# DIO_3.net
KiCad netlist of a schematic drawn in Altium Designer
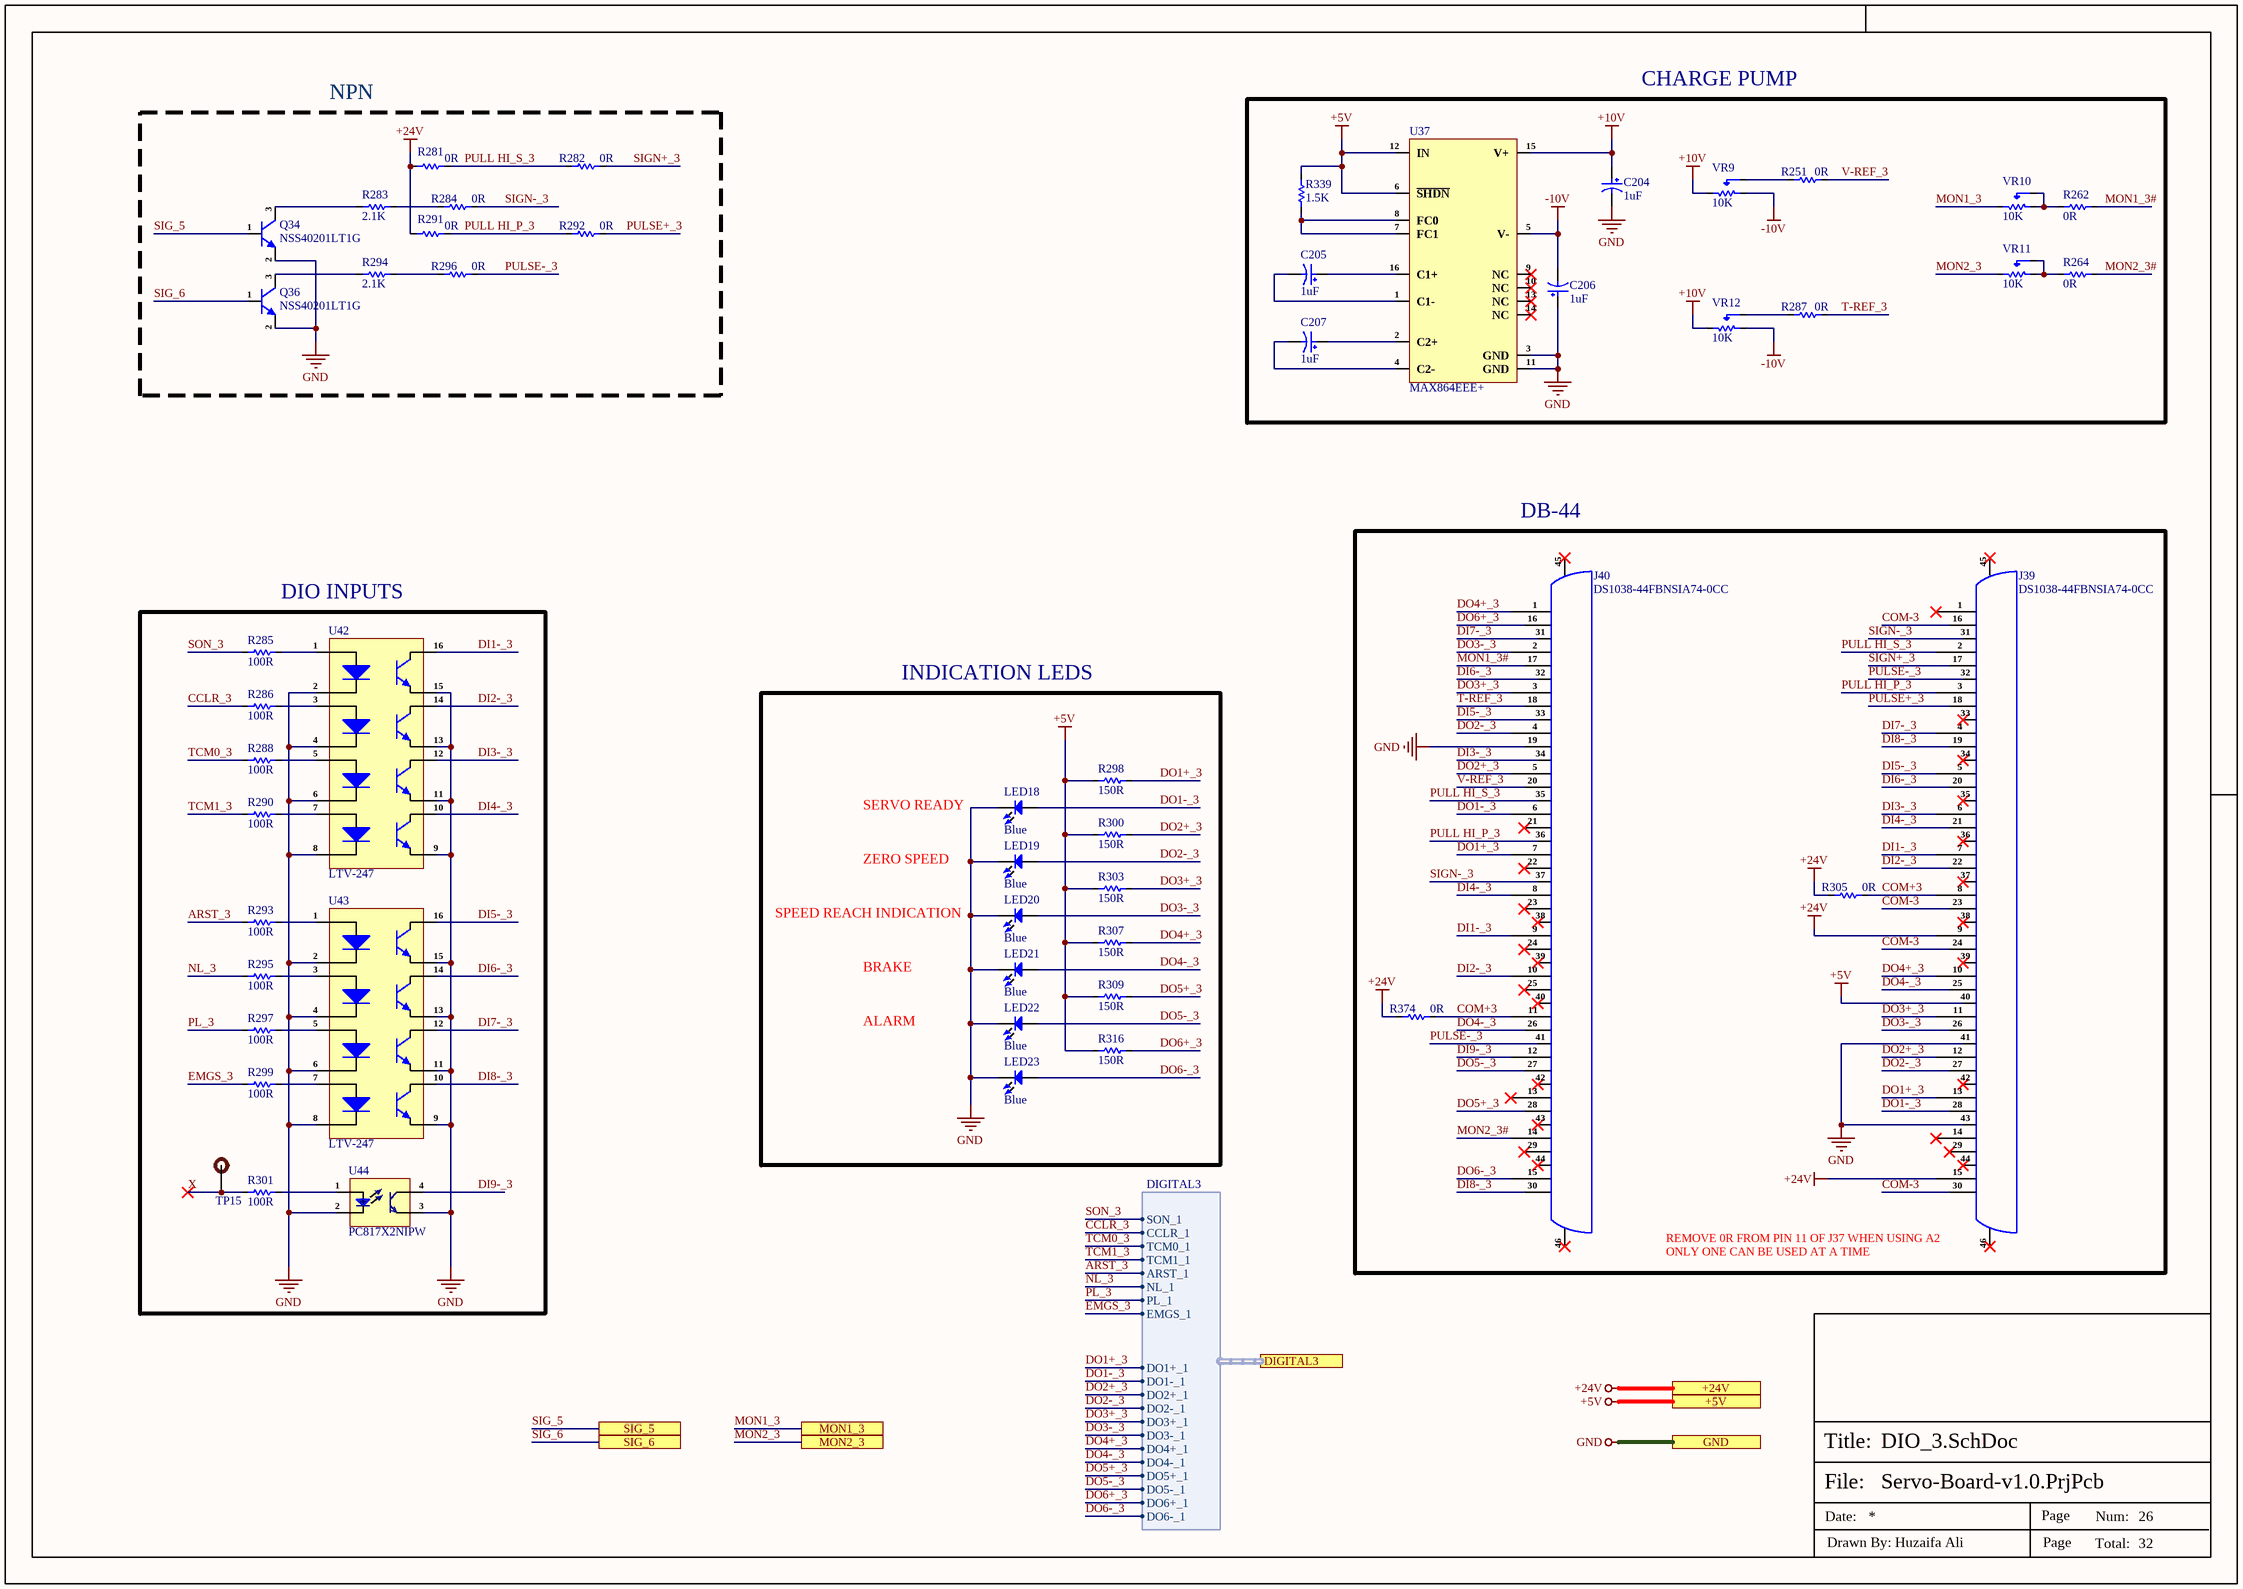
[diagram p0: DIO_3.SchDoc]

(export (version "E")
  (design (tool "Eeschema 10.0.6"))
  (components
    (comp (ref "C204")
      (value "1uF")
      (footprint "RVT1H1R0M0405")
      (description "1uF 50V 8mA@120Hz ±20% SMD,D4xL5.4mm Aluminum Electrolytic Capacitors - SMD ROHS")
      (fields (field (name "LCSC PART NUMBER") "C72491") (field (name "MANUFACTURER") "Roqang"))
      (libsource (lib "") (part "RVT1H1R0M0405_1"))
    )
    (comp (ref "C205")
      (value "1uF")
      (footprint "RVT1H1R0M0405")
      (description "1uF 50V 8mA@120Hz ±20% SMD,D4xL5.4mm Aluminum Electrolytic Capacitors - SMD ROHS")
      (fields (field (name "LCSC PART NUMBER") "C72491") (field (name "MANUFACTURER") "Roqang"))
      (libsource (lib "") (part "RVT1H1R0M0405_2"))
    )
    (comp (ref "C206")
      (value "1uF")
      (footprint "RVT1H1R0M0405")
      (description "1uF 50V 8mA@120Hz ±20% SMD,D4xL5.4mm Aluminum Electrolytic Capacitors - SMD ROHS")
      (fields (field (name "LCSC PART NUMBER") "C72491") (field (name "MANUFACTURER") "Roqang"))
      (libsource (lib "eSpark Libraries") (part "RVT1H1R0M0405"))
    )
    (comp (ref "C207")
      (value "1uF")
      (footprint "RVT1H1R0M0405")
      (description "1uF 50V 8mA@120Hz ±20% SMD,D4xL5.4mm Aluminum Electrolytic Capacitors - SMD ROHS")
      (fields (field (name "LCSC PART NUMBER") "C72491") (field (name "MANUFACTURER") "Roqang"))
      (libsource (lib "") (part "RVT1H1R0M0405_2"))
    )
    (comp (ref "J39")
      (value "DS1038-44FBNSIA74-0CC")
      (footprint "DS1038-44FBNSIA74-0CC")
      (description "44P Female D-Sub Right-Angle 3 1.5A -40℃~+105℃ Push-Pull D-Sub / VGA connector ROHS")
      (fields (field (name "MANUFACTURER") "CONNFLY Elec") (field (name "LCSC PART NUMBER") "C77844"))
      (libsource (lib "eSpark Libraries") (part "DS1038-44FBNSIA74-0CC"))
    )
    (comp (ref "J40")
      (value "DS1038-44FBNSIA74-0CC")
      (footprint "DS1038-44FBNSIA74-0CC")
      (description "44P Female D-Sub Right-Angle 3 1.5A -40℃~+105℃ Push-Pull D-Sub / VGA connector ROHS")
      (fields (field (name "MANUFACTURER") "CONNFLY Elec") (field (name "LCSC PART NUMBER") "C77844"))
      (libsource (lib "eSpark Libraries") (part "DS1038-44FBNSIA74-0CC"))
    )
    (comp (ref "LED18")
      (value "Blue")
      (footprint "LED-0603")
      (description "blue 0603 Light Emitting Diodes (LED) ROHS")
      (fields
        (field (name "MANUFACTURER") "Foshan NationStar Optoelectronics")
        (field (name "MANUFACTURER PART NUMBER") "NCD0603B3")
      )
      (libsource (lib "eSpark Libraries") (part "NCD0603B3"))
    )
    (comp (ref "LED19")
      (value "Blue")
      (footprint "LED-0603")
      (description "blue 0603 Light Emitting Diodes (LED) ROHS")
      (fields
        (field (name "MANUFACTURER") "Foshan NationStar Optoelectronics")
        (field (name "MANUFACTURER PART NUMBER") "NCD0603B3")
      )
      (libsource (lib "eSpark Libraries") (part "NCD0603B3"))
    )
    (comp (ref "LED20")
      (value "Blue")
      (footprint "LED-0603")
      (description "blue 0603 Light Emitting Diodes (LED) ROHS")
      (fields
        (field (name "MANUFACTURER") "Foshan NationStar Optoelectronics")
        (field (name "MANUFACTURER PART NUMBER") "NCD0603B3")
      )
      (libsource (lib "eSpark Libraries") (part "NCD0603B3"))
    )
    (comp (ref "LED21")
      (value "Blue")
      (footprint "LED-0603")
      (description "blue 0603 Light Emitting Diodes (LED) ROHS")
      (fields
        (field (name "MANUFACTURER") "Foshan NationStar Optoelectronics")
        (field (name "MANUFACTURER PART NUMBER") "NCD0603B3")
      )
      (libsource (lib "eSpark Libraries") (part "NCD0603B3"))
    )
    (comp (ref "LED22")
      (value "Blue")
      (footprint "LED-0603")
      (description "blue 0603 Light Emitting Diodes (LED) ROHS")
      (fields
        (field (name "MANUFACTURER") "Foshan NationStar Optoelectronics")
        (field (name "MANUFACTURER PART NUMBER") "NCD0603B3")
      )
      (libsource (lib "eSpark Libraries") (part "NCD0603B3"))
    )
    (comp (ref "LED23")
      (value "Blue")
      (footprint "LED-0603")
      (description "blue 0603 Light Emitting Diodes (LED) ROHS")
      (fields
        (field (name "MANUFACTURER") "Foshan NationStar Optoelectronics")
        (field (name "MANUFACTURER PART NUMBER") "NCD0603B3")
      )
      (libsource (lib "eSpark Libraries") (part "NCD0603B3"))
    )
    (comp (ref "Q34")
      (value "NSS40201LT1G")
      (footprint "SOT-23")
      (description "TRANS NPN 40V 2A SOT23-3")
      (fields (field (name "MANUFACTURER") "ON Semiconductor") (field (name "LCSC PART NUMBER") "C145175"))
      (libsource (lib "eSpark Libraries") (part "NSS40201LT1G"))
    )
    (comp (ref "Q36")
      (value "NSS40201LT1G")
      (footprint "SOT-23")
      (description "TRANS NPN 40V 2A SOT23-3")
      (fields (field (name "MANUFACTURER") "ON Semiconductor") (field (name "LCSC PART NUMBER") "C145175"))
      (libsource (lib "eSpark Libraries") (part "NSS40201LT1G"))
    )
    (comp (ref "R251")
      (value "0R")
      (footprint "Res-0402")
      (description "RES 0 OHM JUMPER 1/16W 0402")
      (fields
        (field (name "MANUFACTURER") "Yageo")
        (field (name "MANUFACTURER PART NUMBER") "RC0402FR-070RL")
      )
      (libsource (lib "eSpark Libraries") (part "RC0402FR-070RL"))
    )
    (comp (ref "R262")
      (value "0R")
      (footprint "Res-0402")
      (description "RES 0 OHM JUMPER 1/16W 0402")
      (fields
        (field (name "MANUFACTURER") "Yageo")
        (field (name "MANUFACTURER PART NUMBER") "RC0402FR-070RL")
      )
      (libsource (lib "eSpark Libraries") (part "RC0402FR-070RL"))
    )
    (comp (ref "R264")
      (value "0R")
      (footprint "Res-0402")
      (description "RES 0 OHM JUMPER 1/16W 0402")
      (fields
        (field (name "MANUFACTURER") "Yageo")
        (field (name "MANUFACTURER PART NUMBER") "RC0402FR-070RL")
      )
      (libsource (lib "eSpark Libraries") (part "RC0402FR-070RL"))
    )
    (comp (ref "R281")
      (value "0R")
      (footprint "Res-0603")
      (description "RES 0 OHM JUMPER 1/10W 0603")
      (fields
        (field (name "MANUFACTURER") "Yageo")
        (field (name "MANUFACTURER PART NUMBER") "RC0603JR-070RL")
      )
      (libsource (lib "eSpark Libraries") (part "RC0603JR-070RL"))
    )
    (comp (ref "R282")
      (value "0R")
      (footprint "Res-0603")
      (description "RES 0 OHM JUMPER 1/10W 0603")
      (fields
        (field (name "MANUFACTURER") "Yageo")
        (field (name "MANUFACTURER PART NUMBER") "RC0603JR-070RL")
      )
      (libsource (lib "eSpark Libraries") (part "RC0603JR-070RL"))
    )
    (comp (ref "R283")
      (value "2.1K")
      (footprint "Res-0603")
      (description "RES SMD 2.1K OHM 0.1% 1/10W 0603")
      (fields
        (field (name "MANUFACTURER") "Yageo")
        (field (name "MANUFACTURER PART NUMBER") "RT0603BRD072K1L")
      )
      (libsource (lib "eSpark Libraries") (part "RT0603BRD072K1L"))
    )
    (comp (ref "R284")
      (value "0R")
      (footprint "Res-0603")
      (description "RES 0 OHM JUMPER 1/10W 0603")
      (fields
        (field (name "MANUFACTURER") "Yageo")
        (field (name "MANUFACTURER PART NUMBER") "RC0603JR-070RL")
      )
      (libsource (lib "eSpark Libraries") (part "RC0603JR-070RL"))
    )
    (comp (ref "R285")
      (value "100R")
      (footprint "Res-0402")
      (description "RES 100 OHM 1% 1/16W 0402")
      (fields
        (field (name "MANUFACTURER") "Yageo")
        (field (name "MANUFACTURER PART NUMBER") "RC0402FR-07100RL")
      )
      (libsource (lib "eSpark Libraries") (part "RC0402FR-07100RL"))
    )
    (comp (ref "R286")
      (value "100R")
      (footprint "Res-0402")
      (description "RES 100 OHM 1% 1/16W 0402")
      (fields
        (field (name "MANUFACTURER") "Yageo")
        (field (name "MANUFACTURER PART NUMBER") "RC0402FR-07100RL")
      )
      (libsource (lib "eSpark Libraries") (part "RC0402FR-07100RL"))
    )
    (comp (ref "R287")
      (value "0R")
      (footprint "Res-0402")
      (description "RES 0 OHM JUMPER 1/16W 0402")
      (fields
        (field (name "MANUFACTURER") "Yageo")
        (field (name "MANUFACTURER PART NUMBER") "RC0402FR-070RL")
      )
      (libsource (lib "eSpark Libraries") (part "RC0402FR-070RL"))
    )
    (comp (ref "R288")
      (value "100R")
      (footprint "Res-0402")
      (description "RES 100 OHM 1% 1/16W 0402")
      (fields
        (field (name "MANUFACTURER") "Yageo")
        (field (name "MANUFACTURER PART NUMBER") "RC0402FR-07100RL")
      )
      (libsource (lib "eSpark Libraries") (part "RC0402FR-07100RL"))
    )
    (comp (ref "R290")
      (value "100R")
      (footprint "Res-0402")
      (description "RES 100 OHM 1% 1/16W 0402")
      (fields
        (field (name "MANUFACTURER") "Yageo")
        (field (name "MANUFACTURER PART NUMBER") "RC0402FR-07100RL")
      )
      (libsource (lib "eSpark Libraries") (part "RC0402FR-07100RL"))
    )
    (comp (ref "R291")
      (value "0R")
      (footprint "Res-0603")
      (description "RES 0 OHM JUMPER 1/10W 0603")
      (fields
        (field (name "MANUFACTURER") "Yageo")
        (field (name "MANUFACTURER PART NUMBER") "RC0603JR-070RL")
      )
      (libsource (lib "eSpark Libraries") (part "RC0603JR-070RL"))
    )
    (comp (ref "R292")
      (value "0R")
      (footprint "Res-0603")
      (description "RES 0 OHM JUMPER 1/10W 0603")
      (fields
        (field (name "MANUFACTURER") "Yageo")
        (field (name "MANUFACTURER PART NUMBER") "RC0603JR-070RL")
      )
      (libsource (lib "eSpark Libraries") (part "RC0603JR-070RL"))
    )
    (comp (ref "R293")
      (value "100R")
      (footprint "Res-0402")
      (description "RES 100 OHM 1% 1/16W 0402")
      (fields
        (field (name "MANUFACTURER") "Yageo")
        (field (name "MANUFACTURER PART NUMBER") "RC0402FR-07100RL")
      )
      (libsource (lib "eSpark Libraries") (part "RC0402FR-07100RL"))
    )
    (comp (ref "R294")
      (value "2.1K")
      (footprint "Res-0603")
      (description "RES SMD 2.1K OHM 0.1% 1/10W 0603")
      (fields
        (field (name "MANUFACTURER") "Yageo")
        (field (name "MANUFACTURER PART NUMBER") "RT0603BRD072K1L")
      )
      (libsource (lib "eSpark Libraries") (part "RT0603BRD072K1L"))
    )
    (comp (ref "R295")
      (value "100R")
      (footprint "Res-0402")
      (description "RES 100 OHM 1% 1/16W 0402")
      (fields
        (field (name "MANUFACTURER") "Yageo")
        (field (name "MANUFACTURER PART NUMBER") "RC0402FR-07100RL")
      )
      (libsource (lib "eSpark Libraries") (part "RC0402FR-07100RL"))
    )
    (comp (ref "R296")
      (value "0R")
      (footprint "Res-0603")
      (description "RES 0 OHM JUMPER 1/10W 0603")
      (fields
        (field (name "MANUFACTURER") "Yageo")
        (field (name "MANUFACTURER PART NUMBER") "RC0603JR-070RL")
      )
      (libsource (lib "eSpark Libraries") (part "RC0603JR-070RL"))
    )
    (comp (ref "R297")
      (value "100R")
      (footprint "Res-0402")
      (description "RES 100 OHM 1% 1/16W 0402")
      (fields
        (field (name "MANUFACTURER") "Yageo")
        (field (name "MANUFACTURER PART NUMBER") "RC0402FR-07100RL")
      )
      (libsource (lib "eSpark Libraries") (part "RC0402FR-07100RL"))
    )
    (comp (ref "R298")
      (value "150R")
      (footprint "Res-0603")
      (description "RES 150 OHM 0.5% 1/10W 0603")
      (fields
        (field (name "MANUFACTURER") "Yageo")
        (field (name "MANUFACTURER PART NUMBER") "RC0603DR-07150RL")
      )
      (libsource (lib "eSpark Libraries") (part "RC0603DR-07150RL"))
    )
    (comp (ref "R299")
      (value "100R")
      (footprint "Res-0402")
      (description "RES 100 OHM 1% 1/16W 0402")
      (fields
        (field (name "MANUFACTURER") "Yageo")
        (field (name "MANUFACTURER PART NUMBER") "RC0402FR-07100RL")
      )
      (libsource (lib "eSpark Libraries") (part "RC0402FR-07100RL"))
    )
    (comp (ref "R300")
      (value "150R")
      (footprint "Res-0603")
      (description "RES 150 OHM 0.5% 1/10W 0603")
      (fields
        (field (name "MANUFACTURER") "Yageo")
        (field (name "MANUFACTURER PART NUMBER") "RC0603DR-07150RL")
      )
      (libsource (lib "eSpark Libraries") (part "RC0603DR-07150RL"))
    )
    (comp (ref "R301")
      (value "100R")
      (footprint "Res-0402")
      (description "RES 100 OHM 1% 1/16W 0402")
      (fields
        (field (name "MANUFACTURER") "Yageo")
        (field (name "MANUFACTURER PART NUMBER") "RC0402FR-07100RL")
      )
      (libsource (lib "eSpark Libraries") (part "RC0402FR-07100RL"))
    )
    (comp (ref "R303")
      (value "150R")
      (footprint "Res-0603")
      (description "RES 150 OHM 0.5% 1/10W 0603")
      (fields
        (field (name "MANUFACTURER") "Yageo")
        (field (name "MANUFACTURER PART NUMBER") "RC0603DR-07150RL")
      )
      (libsource (lib "eSpark Libraries") (part "RC0603DR-07150RL"))
    )
    (comp (ref "R305")
      (value "0R")
      (footprint "Res-0402")
      (description "RES 0 OHM JUMPER 1/16W 0402")
      (fields
        (field (name "MANUFACTURER") "Yageo")
        (field (name "MANUFACTURER PART NUMBER") "RC0402FR-070RL")
      )
      (libsource (lib "eSpark Libraries") (part "RC0402FR-070RL"))
    )
    (comp (ref "R307")
      (value "150R")
      (footprint "Res-0603")
      (description "RES 150 OHM 0.5% 1/10W 0603")
      (fields
        (field (name "MANUFACTURER") "Yageo")
        (field (name "MANUFACTURER PART NUMBER") "RC0603DR-07150RL")
      )
      (libsource (lib "eSpark Libraries") (part "RC0603DR-07150RL"))
    )
    (comp (ref "R309")
      (value "150R")
      (footprint "Res-0603")
      (description "RES 150 OHM 0.5% 1/10W 0603")
      (fields
        (field (name "MANUFACTURER") "Yageo")
        (field (name "MANUFACTURER PART NUMBER") "RC0603DR-07150RL")
      )
      (libsource (lib "eSpark Libraries") (part "RC0603DR-07150RL"))
    )
    (comp (ref "R316")
      (value "150R")
      (footprint "Res-0603")
      (description "RES 150 OHM 0.5% 1/10W 0603")
      (fields
        (field (name "MANUFACTURER") "Yageo")
        (field (name "MANUFACTURER PART NUMBER") "RC0603DR-07150RL")
      )
      (libsource (lib "eSpark Libraries") (part "RC0603DR-07150RL"))
    )
    (comp (ref "R339")
      (value "1.5K")
      (footprint "Res-0402")
      (description "RES 1.5K OHM 1% 1/16W 0402")
      (fields
        (field (name "MANUFACTURER") "Yageo")
        (field (name "MANUFACTURER PART NUMBER") "RC0402FR-071K5L")
      )
      (libsource (lib "eSpark Libraries") (part "RC0402FR-071K5L"))
    )
    (comp (ref "R374")
      (value "0R")
      (footprint "Res-0402")
      (description "RES 0 OHM JUMPER 1/16W 0402")
      (fields
        (field (name "MANUFACTURER") "Yageo")
        (field (name "MANUFACTURER PART NUMBER") "RC0402FR-070RL")
      )
      (libsource (lib "eSpark Libraries") (part "RC0402FR-070RL"))
    )
    (comp (ref "TP15")
      (value "TEST POINT")
      (footprint "Test-point")
      (description "Test Point ON")
      (libsource (lib "eSpark Libraries") (part "TEST POINT"))
    )
    (comp (ref "U37")
      (value "MAX864EEE+")
      (footprint "16-QSOP")
      (description "IC REG CHARGE PUMP INV 16QSOP")
      (fields (field (name "MANUFACTURER") "Maxim"))
      (libsource (lib "eSpark Libraries") (part "MAX864EEE+"))
    )
    (comp (ref "U42")
      (value "LTV-247")
      (footprint "16-SO")
      (description "OPTOISO 3.75KV 4CH TRANS 16SO")
      (fields (field (name "MANUFACTURER") "Vishay Lite-On") (field (name "LCSC PART NUMBER") "C115451"))
      (libsource (lib "eSpark Libraries") (part "LTV-247"))
    )
    (comp (ref "U43")
      (value "LTV-247")
      (footprint "16-SO")
      (description "OPTOISO 3.75KV 4CH TRANS 16SO")
      (fields (field (name "MANUFACTURER") "Vishay Lite-On") (field (name "LCSC PART NUMBER") "C115451"))
      (libsource (lib "eSpark Libraries") (part "LTV-247"))
    )
    (comp (ref "U44")
      (value "PC817X2NIPW")
      (footprint "PC817X2NIPW")
      (description "Optoisolator Output Channel 4-SMD")
      (fields (field (name "MANUFACTURER") "Sharp") (field (name "LCSC PART NUMBER") "C2840443"))
      (libsource (lib "eSpark Libraries") (part "PC817X2NIPW"))
    )
    (comp (ref "VR9")
      (value "10K")
      (footprint "3362P-1-103")
      (description "TRIMMER 10K OHM 0.5W PC PIN TOP")
      (fields (field (name "LCSC PART NUMBER") "C118956") (field (name "MANUFACTURER") "Bourns"))
      (libsource (lib "eSpark Libraries") (part "3362P-1-103"))
    )
    (comp (ref "VR10")
      (value "10K")
      (footprint "3362P-1-103")
      (description "TRIMMER 10K OHM 0.5W PC PIN TOP")
      (fields (field (name "LCSC PART NUMBER") "C118956") (field (name "MANUFACTURER") "Bourns"))
      (libsource (lib "eSpark Libraries") (part "3362P-1-103"))
    )
    (comp (ref "VR11")
      (value "10K")
      (footprint "3362P-1-103")
      (description "TRIMMER 10K OHM 0.5W PC PIN TOP")
      (fields (field (name "LCSC PART NUMBER") "C118956") (field (name "MANUFACTURER") "Bourns"))
      (libsource (lib "eSpark Libraries") (part "3362P-1-103"))
    )
    (comp (ref "VR12")
      (value "10K")
      (footprint "3362P-1-103")
      (description "TRIMMER 10K OHM 0.5W PC PIN TOP")
      (fields (field (name "LCSC PART NUMBER") "C118956") (field (name "MANUFACTURER") "Bourns"))
      (libsource (lib "eSpark Libraries") (part "3362P-1-103"))
    )
  )
  (nets
    (net (code "2") (name "+5V") (class "Default")
      (node (ref "J39") (pin "40") (pinfunction "40_40") (pintype "passive"))
      (node (ref "R298") (pin "1") (pinfunction "1_1") (pintype "passive"))
      (node (ref "R300") (pin "1") (pinfunction "1_1") (pintype "passive"))
      (node (ref "R303") (pin "1") (pinfunction "1_1") (pintype "passive"))
      (node (ref "R307") (pin "1") (pinfunction "1_1") (pintype "passive"))
      (node (ref "R309") (pin "1") (pinfunction "1_1") (pintype "passive"))
      (node (ref "R316") (pin "1") (pinfunction "1_1") (pintype "passive"))
      (node (ref "R339") (pin "2") (pinfunction "2_2") (pintype "passive"))
      (node (ref "U37") (pin "12") (pinfunction "IN_12") (pintype "passive"))
      (node (ref "U37") (pin "6") (pinfunction "~{SHDN}_6") (pintype "passive"))
    )
    (net (code "3") (name "+10V") (class "Default")
      (node (ref "C204") (pin "1") (pintype "passive"))
      (node (ref "U37") (pin "15") (pinfunction "V+_15") (pintype "passive"))
      (node (ref "VR12") (pin "3") (pinfunction "CW_3") (pintype "passive"))
      (node (ref "VR9") (pin "3") (pinfunction "CW_3") (pintype "passive"))
    )
    (net (code "4") (name "+24V") (class "Default")
      (node (ref "J39") (pin "15") (pinfunction "15_15") (pintype "passive"))
      (node (ref "J39") (pin "9") (pinfunction "9_9") (pintype "passive"))
      (node (ref "R281") (pin "1") (pinfunction "1_1") (pintype "passive"))
      (node (ref "R291") (pin "1") (pinfunction "1_1") (pintype "passive"))
      (node (ref "R305") (pin "1") (pinfunction "1_1") (pintype "passive"))
      (node (ref "R374") (pin "1") (pinfunction "1_1") (pintype "passive"))
    )
    (net (code "5") (name "-10V") (class "Default")
      (node (ref "C206") (pin "2") (pintype "passive"))
      (node (ref "U37") (pin "5") (pinfunction "V-_5") (pintype "passive"))
      (node (ref "VR12") (pin "1") (pinfunction "CCW_1") (pintype "passive"))
      (node (ref "VR9") (pin "1") (pinfunction "CCW_1") (pintype "passive"))
    )
    (net (code "6") (name "/ARST_3") (class "Default")
      (node (ref "R293") (pin "1") (pinfunction "1_1") (pintype "passive"))
    )
    (net (code "7") (name "/CCLR_3") (class "Default")
      (node (ref "R286") (pin "1") (pinfunction "1_1") (pintype "passive"))
    )
    (net (code "8") (name "/COM+3") (class "Default")
      (node (ref "J39") (pin "8") (pinfunction "8_8") (pintype "passive"))
      (node (ref "J40") (pin "11") (pinfunction "11_11") (pintype "passive"))
      (node (ref "R305") (pin "2") (pinfunction "2_2") (pintype "passive"))
      (node (ref "R374") (pin "2") (pinfunction "2_2") (pintype "passive"))
    )
    (net (code "9") (name "/COM-3") (class "Default")
      (node (ref "J39") (pin "16") (pinfunction "16_16") (pintype "passive"))
      (node (ref "J39") (pin "23") (pinfunction "23_23") (pintype "passive"))
      (node (ref "J39") (pin "24") (pinfunction "24_24") (pintype "passive"))
      (node (ref "J39") (pin "30") (pinfunction "30_30") (pintype "passive"))
    )
    (net (code "10") (name "/DI1-_3") (class "Default")
      (node (ref "J39") (pin "7") (pinfunction "7_7") (pintype "passive"))
      (node (ref "J40") (pin "9") (pinfunction "9_9") (pintype "passive"))
      (node (ref "U42") (pin "16") (pinfunction "C_16") (pintype "passive"))
    )
    (net (code "11") (name "/DI2-_3") (class "Default")
      (node (ref "J39") (pin "22") (pinfunction "22_22") (pintype "passive"))
      (node (ref "J40") (pin "10") (pinfunction "10_10") (pintype "passive"))
      (node (ref "U42") (pin "14") (pinfunction "C_14") (pintype "passive"))
    )
    (net (code "12") (name "/DI3-_3") (class "Default")
      (node (ref "J39") (pin "6") (pinfunction "6_6") (pintype "passive"))
      (node (ref "J40") (pin "34") (pinfunction "34_34") (pintype "passive"))
      (node (ref "U42") (pin "12") (pinfunction "C_12") (pintype "passive"))
    )
    (net (code "13") (name "/DI4-_3") (class "Default")
      (node (ref "J39") (pin "21") (pinfunction "21_21") (pintype "passive"))
      (node (ref "J40") (pin "8") (pinfunction "8_8") (pintype "passive"))
      (node (ref "U42") (pin "10") (pinfunction "C_10") (pintype "passive"))
    )
    (net (code "14") (name "/DI5-_3") (class "Default")
      (node (ref "J39") (pin "5") (pinfunction "5_5") (pintype "passive"))
      (node (ref "J40") (pin "33") (pinfunction "33_33") (pintype "passive"))
      (node (ref "U43") (pin "16") (pinfunction "C_16") (pintype "passive"))
    )
    (net (code "15") (name "/DI6-_3") (class "Default")
      (node (ref "J39") (pin "20") (pinfunction "20_20") (pintype "passive"))
      (node (ref "J40") (pin "32") (pinfunction "32_32") (pintype "passive"))
      (node (ref "U43") (pin "14") (pinfunction "C_14") (pintype "passive"))
    )
    (net (code "16") (name "/DI7-_3") (class "Default")
      (node (ref "J39") (pin "4") (pinfunction "4_4") (pintype "passive"))
      (node (ref "J40") (pin "31") (pinfunction "31_31") (pintype "passive"))
      (node (ref "U43") (pin "12") (pinfunction "C_12") (pintype "passive"))
    )
    (net (code "17") (name "/DI8-_3") (class "Default")
      (node (ref "J39") (pin "19") (pinfunction "19_19") (pintype "passive"))
      (node (ref "J40") (pin "30") (pinfunction "30_30") (pintype "passive"))
      (node (ref "U43") (pin "10") (pinfunction "C_10") (pintype "passive"))
    )
    (net (code "18") (name "/DI9-_3") (class "Default")
      (node (ref "J40") (pin "12") (pinfunction "12_12") (pintype "passive"))
      (node (ref "U44") (pin "4") (pinfunction "C_4") (pintype "passive"))
    )
    (net (code "19") (name "/DO1+_3") (class "Default")
      (node (ref "J39") (pin "13") (pinfunction "13_13") (pintype "passive"))
      (node (ref "J40") (pin "7") (pinfunction "7_7") (pintype "passive"))
      (node (ref "R298") (pin "2") (pinfunction "2_2") (pintype "passive"))
    )
    (net (code "20") (name "/DO1-_3") (class "Default")
      (node (ref "J39") (pin "28") (pinfunction "28_28") (pintype "passive"))
      (node (ref "J40") (pin "6") (pinfunction "6_6") (pintype "passive"))
      (node (ref "LED18") (pin "1") (pinfunction "1_1") (pintype "passive"))
    )
    (net (code "21") (name "/DO2+_3") (class "Default")
      (node (ref "J39") (pin "12") (pinfunction "12_12") (pintype "passive"))
      (node (ref "J40") (pin "5") (pinfunction "5_5") (pintype "passive"))
      (node (ref "R300") (pin "2") (pinfunction "2_2") (pintype "passive"))
    )
    (net (code "22") (name "/DO2-_3") (class "Default")
      (node (ref "J39") (pin "27") (pinfunction "27_27") (pintype "passive"))
      (node (ref "J40") (pin "4") (pinfunction "4_4") (pintype "passive"))
      (node (ref "LED19") (pin "1") (pinfunction "1_1") (pintype "passive"))
    )
    (net (code "23") (name "/DO3+_3") (class "Default")
      (node (ref "J39") (pin "11") (pinfunction "11_11") (pintype "passive"))
      (node (ref "J40") (pin "3") (pinfunction "3_3") (pintype "passive"))
      (node (ref "R303") (pin "2") (pinfunction "2_2") (pintype "passive"))
    )
    (net (code "24") (name "/DO3-_3") (class "Default")
      (node (ref "J39") (pin "26") (pinfunction "26_26") (pintype "passive"))
      (node (ref "J40") (pin "2") (pinfunction "2_2") (pintype "passive"))
      (node (ref "LED20") (pin "1") (pinfunction "1_1") (pintype "passive"))
    )
    (net (code "25") (name "/DO4+_3") (class "Default")
      (node (ref "J39") (pin "10") (pinfunction "10_10") (pintype "passive"))
      (node (ref "J40") (pin "1") (pinfunction "1_1") (pintype "passive"))
      (node (ref "R307") (pin "2") (pinfunction "2_2") (pintype "passive"))
    )
    (net (code "26") (name "/DO4-_3") (class "Default")
      (node (ref "J39") (pin "25") (pinfunction "25_25") (pintype "passive"))
      (node (ref "J40") (pin "26") (pinfunction "26_26") (pintype "passive"))
      (node (ref "LED21") (pin "1") (pinfunction "1_1") (pintype "passive"))
    )
    (net (code "27") (name "/DO5+_3") (class "Default")
      (node (ref "J40") (pin "28") (pinfunction "28_28") (pintype "passive"))
      (node (ref "R309") (pin "2") (pinfunction "2_2") (pintype "passive"))
    )
    (net (code "28") (name "/DO5-_3") (class "Default")
      (node (ref "J40") (pin "27") (pinfunction "27_27") (pintype "passive"))
      (node (ref "LED22") (pin "1") (pinfunction "1_1") (pintype "passive"))
    )
    (net (code "29") (name "/DO6+_3") (class "Default")
      (node (ref "J40") (pin "16") (pinfunction "16_16") (pintype "passive"))
      (node (ref "R316") (pin "2") (pinfunction "2_2") (pintype "passive"))
    )
    (net (code "30") (name "/DO6-_3") (class "Default")
      (node (ref "J40") (pin "15") (pinfunction "15_15") (pintype "passive"))
      (node (ref "LED23") (pin "1") (pinfunction "1_1") (pintype "passive"))
    )
    (net (code "31") (name "/EMGS_3") (class "Default")
      (node (ref "R299") (pin "1") (pinfunction "1_1") (pintype "passive"))
    )
    (net (code "32") (name "/MON1_3") (class "Default")
      (node (ref "VR10") (pin "3") (pinfunction "CW_3") (pintype "passive"))
    )
    (net (code "33") (name "/MON1_3#") (class "Default")
      (node (ref "J40") (pin "17") (pinfunction "17_17") (pintype "passive"))
      (node (ref "R262") (pin "2") (pinfunction "2_2") (pintype "passive"))
    )
    (net (code "34") (name "/MON2_3") (class "Default")
      (node (ref "VR11") (pin "3") (pinfunction "CW_3") (pintype "passive"))
    )
    (net (code "35") (name "/MON2_3#") (class "Default")
      (node (ref "J40") (pin "14") (pinfunction "14_14") (pintype "passive"))
      (node (ref "R264") (pin "2") (pinfunction "2_2") (pintype "passive"))
    )
    (net (code "36") (name "/NL_3") (class "Default")
      (node (ref "R295") (pin "1") (pinfunction "1_1") (pintype "passive"))
    )
    (net (code "37") (name "/PL_3") (class "Default")
      (node (ref "R297") (pin "1") (pinfunction "1_1") (pintype "passive"))
    )
    (net (code "38") (name "/PULL HI_P_3") (class "Default")
      (node (ref "J39") (pin "3") (pinfunction "3_3") (pintype "passive"))
      (node (ref "J40") (pin "36") (pinfunction "36_36") (pintype "passive"))
      (node (ref "R291") (pin "2") (pinfunction "2_2") (pintype "passive"))
      (node (ref "R292") (pin "1") (pinfunction "1_1") (pintype "passive"))
    )
    (net (code "39") (name "/PULL HI_S_3") (class "Default")
      (node (ref "J39") (pin "2") (pinfunction "2_2") (pintype "passive"))
      (node (ref "J40") (pin "35") (pinfunction "35_35") (pintype "passive"))
      (node (ref "R281") (pin "2") (pinfunction "2_2") (pintype "passive"))
      (node (ref "R282") (pin "1") (pinfunction "1_1") (pintype "passive"))
    )
    (net (code "40") (name "/PULSE+_3") (class "Default")
      (node (ref "J39") (pin "18") (pinfunction "18_18") (pintype "passive"))
      (node (ref "R292") (pin "2") (pinfunction "2_2") (pintype "passive"))
    )
    (net (code "41") (name "/PULSE-_3") (class "Default")
      (node (ref "J39") (pin "32") (pinfunction "32_32") (pintype "passive"))
      (node (ref "J40") (pin "41") (pinfunction "41_41") (pintype "passive"))
      (node (ref "R296") (pin "2") (pinfunction "2_2") (pintype "passive"))
    )
    (net (code "42") (name "/SIGN+_3") (class "Default")
      (node (ref "J39") (pin "17") (pinfunction "17_17") (pintype "passive"))
      (node (ref "R282") (pin "2") (pinfunction "2_2") (pintype "passive"))
    )
    (net (code "43") (name "/SIGN-_3") (class "Default")
      (node (ref "J39") (pin "31") (pinfunction "31_31") (pintype "passive"))
      (node (ref "J40") (pin "37") (pinfunction "37_37") (pintype "passive"))
      (node (ref "R284") (pin "2") (pinfunction "2_2") (pintype "passive"))
    )
    (net (code "44") (name "/SIG_5") (class "Default")
      (node (ref "Q34") (pin "1") (pinfunction "B_1") (pintype "passive"))
    )
    (net (code "45") (name "/SIG_6") (class "Default")
      (node (ref "Q36") (pin "1") (pinfunction "B_1") (pintype "passive"))
    )
    (net (code "46") (name "/SON_3") (class "Default")
      (node (ref "R285") (pin "1") (pinfunction "1_1") (pintype "passive"))
    )
    (net (code "47") (name "/T-REF_3") (class "Default")
      (node (ref "J40") (pin "18") (pinfunction "18_18") (pintype "passive"))
      (node (ref "R287") (pin "2") (pinfunction "2_2") (pintype "passive"))
    )
    (net (code "48") (name "/TCM0_3") (class "Default")
      (node (ref "R288") (pin "1") (pinfunction "1_1") (pintype "passive"))
    )
    (net (code "49") (name "/TCM1_3") (class "Default")
      (node (ref "R290") (pin "1") (pinfunction "1_1") (pintype "passive"))
    )
    (net (code "50") (name "/V-REF_3") (class "Default")
      (node (ref "J40") (pin "20") (pinfunction "20_20") (pintype "passive"))
      (node (ref "R251") (pin "2") (pinfunction "2_2") (pintype "passive"))
    )
    (net (code "51") (name "/X") (class "Default")
      (node (ref "R301") (pin "1") (pinfunction "1_1") (pintype "passive"))
      (node (ref "TP15") (pin "1") (pinfunction "1_1") (pintype "passive"))
    )
    (net (code "53") (name "GND") (class "Default")
      (node (ref "C204") (pin "2") (pintype "passive"))
      (node (ref "C206") (pin "1") (pintype "passive"))
      (node (ref "J39") (pin "41") (pinfunction "41_41") (pintype "passive"))
      (node (ref "J39") (pin "43") (pinfunction "43_43") (pintype "passive"))
      (node (ref "J40") (pin "19") (pinfunction "19_19") (pintype "passive"))
      (node (ref "LED18") (pin "2") (pinfunction "2_2") (pintype "passive"))
      (node (ref "LED19") (pin "2") (pinfunction "2_2") (pintype "passive"))
      (node (ref "LED20") (pin "2") (pinfunction "2_2") (pintype "passive"))
      (node (ref "LED21") (pin "2") (pinfunction "2_2") (pintype "passive"))
      (node (ref "LED22") (pin "2") (pinfunction "2_2") (pintype "passive"))
      (node (ref "LED23") (pin "2") (pinfunction "2_2") (pintype "passive"))
      (node (ref "Q34") (pin "2") (pinfunction "E_2") (pintype "passive"))
      (node (ref "Q36") (pin "2") (pinfunction "E_2") (pintype "passive"))
      (node (ref "U37") (pin "11") (pinfunction "GND_11") (pintype "passive"))
      (node (ref "U37") (pin "3") (pinfunction "GND_3") (pintype "passive"))
      (node (ref "U42") (pin "11") (pinfunction "E_11") (pintype "passive"))
      (node (ref "U42") (pin "13") (pinfunction "E_13") (pintype "passive"))
      (node (ref "U42") (pin "15") (pinfunction "E_15") (pintype "passive"))
      (node (ref "U42") (pin "2") (pinfunction "K_2") (pintype "passive"))
      (node (ref "U42") (pin "4") (pinfunction "K_4") (pintype "passive"))
      (node (ref "U42") (pin "6") (pinfunction "K_6") (pintype "passive"))
      (node (ref "U42") (pin "8") (pinfunction "K_8") (pintype "passive"))
      (node (ref "U42") (pin "9") (pinfunction "E_9") (pintype "passive"))
      (node (ref "U43") (pin "11") (pinfunction "E_11") (pintype "passive"))
      (node (ref "U43") (pin "13") (pinfunction "E_13") (pintype "passive"))
      (node (ref "U43") (pin "15") (pinfunction "E_15") (pintype "passive"))
      (node (ref "U43") (pin "2") (pinfunction "K_2") (pintype "passive"))
      (node (ref "U43") (pin "4") (pinfunction "K_4") (pintype "passive"))
      (node (ref "U43") (pin "6") (pinfunction "K_6") (pintype "passive"))
      (node (ref "U43") (pin "8") (pinfunction "K_8") (pintype "passive"))
      (node (ref "U43") (pin "9") (pinfunction "E_9") (pintype "passive"))
      (node (ref "U44") (pin "2") (pinfunction "Ca_2") (pintype "passive"))
      (node (ref "U44") (pin "3") (pinfunction "E_3") (pintype "passive"))
    )
    (net (code "54") (name "Net-(Q34-C)") (class "Default")
      (node (ref "Q34") (pin "3") (pinfunction "C_3") (pintype "passive"))
      (node (ref "R283") (pin "1") (pinfunction "1_1") (pintype "passive"))
    )
    (net (code "55") (name "Net-(Q36-C)") (class "Default")
      (node (ref "Q36") (pin "3") (pinfunction "C_3") (pintype "passive"))
      (node (ref "R294") (pin "1") (pinfunction "1_1") (pintype "passive"))
    )
    (net (code "56") (name "Net-(R283-Pad2)") (class "Default")
      (node (ref "R283") (pin "2") (pinfunction "2_2") (pintype "passive"))
      (node (ref "R284") (pin "1") (pinfunction "1_1") (pintype "passive"))
    )
    (net (code "57") (name "Net-(R285-Pad2)") (class "Default")
      (node (ref "R285") (pin "2") (pinfunction "2_2") (pintype "passive"))
      (node (ref "U42") (pin "1") (pinfunction "A_1") (pintype "passive"))
    )
    (net (code "58") (name "Net-(R286-Pad2)") (class "Default")
      (node (ref "R286") (pin "2") (pinfunction "2_2") (pintype "passive"))
      (node (ref "U42") (pin "3") (pinfunction "A_3") (pintype "passive"))
    )
    (net (code "59") (name "Net-(R288-Pad2)") (class "Default")
      (node (ref "R288") (pin "2") (pinfunction "2_2") (pintype "passive"))
      (node (ref "U42") (pin "5") (pinfunction "A_5") (pintype "passive"))
    )
    (net (code "60") (name "Net-(R290-Pad2)") (class "Default")
      (node (ref "R290") (pin "2") (pinfunction "2_2") (pintype "passive"))
      (node (ref "U42") (pin "7") (pinfunction "A_7") (pintype "passive"))
    )
    (net (code "61") (name "Net-(R293-Pad2)") (class "Default")
      (node (ref "R293") (pin "2") (pinfunction "2_2") (pintype "passive"))
      (node (ref "U43") (pin "1") (pinfunction "A_1") (pintype "passive"))
    )
    (net (code "62") (name "Net-(R294-Pad2)") (class "Default")
      (node (ref "R294") (pin "2") (pinfunction "2_2") (pintype "passive"))
      (node (ref "R296") (pin "1") (pinfunction "1_1") (pintype "passive"))
    )
    (net (code "63") (name "Net-(R295-Pad2)") (class "Default")
      (node (ref "R295") (pin "2") (pinfunction "2_2") (pintype "passive"))
      (node (ref "U43") (pin "3") (pinfunction "A_3") (pintype "passive"))
    )
    (net (code "64") (name "Net-(R297-Pad2)") (class "Default")
      (node (ref "R297") (pin "2") (pinfunction "2_2") (pintype "passive"))
      (node (ref "U43") (pin "5") (pinfunction "A_5") (pintype "passive"))
    )
    (net (code "65") (name "Net-(R299-Pad2)") (class "Default")
      (node (ref "R299") (pin "2") (pinfunction "2_2") (pintype "passive"))
      (node (ref "U43") (pin "7") (pinfunction "A_7") (pintype "passive"))
    )
    (net (code "66") (name "Net-(U37-C1+)") (class "Default")
      (node (ref "C205") (pin "1") (pintype "passive"))
      (node (ref "U37") (pin "16") (pinfunction "C1+_16") (pintype "passive"))
    )
    (net (code "67") (name "Net-(U37-C1-)") (class "Default")
      (node (ref "C205") (pin "2") (pintype "passive"))
      (node (ref "U37") (pin "1") (pinfunction "C1-_1") (pintype "passive"))
    )
    (net (code "68") (name "Net-(U37-C2+)") (class "Default")
      (node (ref "C207") (pin "1") (pintype "passive"))
      (node (ref "U37") (pin "2") (pinfunction "C2+_2") (pintype "passive"))
    )
    (net (code "69") (name "Net-(U37-C2-)") (class "Default")
      (node (ref "C207") (pin "2") (pintype "passive"))
      (node (ref "U37") (pin "4") (pinfunction "C2-_4") (pintype "passive"))
    )
    (net (code "70") (name "Net-(U37-FC0)") (class "Default")
      (node (ref "R339") (pin "1") (pinfunction "1_1") (pintype "passive"))
      (node (ref "U37") (pin "7") (pinfunction "FC1_7") (pintype "passive"))
      (node (ref "U37") (pin "8") (pinfunction "FC0_8") (pintype "passive"))
    )
    (net (code "71") (name "Net-(U44-An)") (class "Default")
      (node (ref "R301") (pin "2") (pinfunction "2_2") (pintype "passive"))
      (node (ref "U44") (pin "1") (pinfunction "An_1") (pintype "passive"))
    )
    (net (code "72") (name "Net-(VR9-Wiper)") (class "Default")
      (node (ref "R251") (pin "1") (pinfunction "1_1") (pintype "passive"))
      (node (ref "VR9") (pin "2") (pinfunction "Wiper_2") (pintype "passive"))
    )
    (net (code "73") (name "Net-(VR10-CCW)") (class "Default")
      (node (ref "R262") (pin "1") (pinfunction "1_1") (pintype "passive"))
      (node (ref "VR10") (pin "1") (pinfunction "CCW_1") (pintype "passive"))
      (node (ref "VR10") (pin "2") (pinfunction "Wiper_2") (pintype "passive"))
    )
    (net (code "74") (name "Net-(VR11-CCW)") (class "Default")
      (node (ref "R264") (pin "1") (pinfunction "1_1") (pintype "passive"))
      (node (ref "VR11") (pin "1") (pinfunction "CCW_1") (pintype "passive"))
      (node (ref "VR11") (pin "2") (pinfunction "Wiper_2") (pintype "passive"))
    )
    (net (code "75") (name "Net-(VR12-Wiper)") (class "Default")
      (node (ref "R287") (pin "1") (pinfunction "1_1") (pintype "passive"))
      (node (ref "VR12") (pin "2") (pinfunction "Wiper_2") (pintype "passive"))
    )
    (net (code "76") (name "unconnected-(J39-Pad1)") (class "Default")
      (node (ref "J39") (pin "1") (pinfunction "1_1") (pintype "passive+no_connect"))
    )
    (net (code "77") (name "unconnected-(J39-Pad14)") (class "Default")
      (node (ref "J39") (pin "14") (pinfunction "14_14") (pintype "passive+no_connect"))
    )
    (net (code "78") (name "unconnected-(J39-Pad29)") (class "Default")
      (node (ref "J39") (pin "29") (pinfunction "29_29") (pintype "passive+no_connect"))
    )
    (net (code "79") (name "unconnected-(J39-Pad33)") (class "Default")
      (node (ref "J39") (pin "33") (pinfunction "33_33") (pintype "passive+no_connect"))
    )
    (net (code "80") (name "unconnected-(J39-Pad34)") (class "Default")
      (node (ref "J39") (pin "34") (pinfunction "34_34") (pintype "passive+no_connect"))
    )
    (net (code "81") (name "unconnected-(J39-Pad35)") (class "Default")
      (node (ref "J39") (pin "35") (pinfunction "35_35") (pintype "passive+no_connect"))
    )
    (net (code "82") (name "unconnected-(J39-Pad36)") (class "Default")
      (node (ref "J39") (pin "36") (pinfunction "36_36") (pintype "passive+no_connect"))
    )
    (net (code "83") (name "unconnected-(J39-Pad37)") (class "Default")
      (node (ref "J39") (pin "37") (pinfunction "37_37") (pintype "passive+no_connect"))
    )
    (net (code "84") (name "unconnected-(J39-Pad38)") (class "Default")
      (node (ref "J39") (pin "38") (pinfunction "38_38") (pintype "passive+no_connect"))
    )
    (net (code "85") (name "unconnected-(J39-Pad39)") (class "Default")
      (node (ref "J39") (pin "39") (pinfunction "39_39") (pintype "passive+no_connect"))
    )
    (net (code "86") (name "unconnected-(J39-Pad42)") (class "Default")
      (node (ref "J39") (pin "42") (pinfunction "42_42") (pintype "passive+no_connect"))
    )
    (net (code "87") (name "unconnected-(J39-Pad44)") (class "Default")
      (node (ref "J39") (pin "44") (pinfunction "44_44") (pintype "passive+no_connect"))
    )
    (net (code "88") (name "unconnected-(J39-Pad45)") (class "Default")
      (node (ref "J39") (pin "45") (pinfunction "45_45") (pintype "passive+no_connect"))
    )
    (net (code "89") (name "unconnected-(J39-Pad46)") (class "Default")
      (node (ref "J39") (pin "46") (pinfunction "46_46") (pintype "passive+no_connect"))
    )
    (net (code "90") (name "unconnected-(J40-Pad13)") (class "Default")
      (node (ref "J40") (pin "13") (pinfunction "13_13") (pintype "passive+no_connect"))
    )
    (net (code "91") (name "unconnected-(J40-Pad21)") (class "Default")
      (node (ref "J40") (pin "21") (pinfunction "21_21") (pintype "passive+no_connect"))
    )
    (net (code "92") (name "unconnected-(J40-Pad22)") (class "Default")
      (node (ref "J40") (pin "22") (pinfunction "22_22") (pintype "passive+no_connect"))
    )
    (net (code "93") (name "unconnected-(J40-Pad23)") (class "Default")
      (node (ref "J40") (pin "23") (pinfunction "23_23") (pintype "passive+no_connect"))
    )
    (net (code "94") (name "unconnected-(J40-Pad24)") (class "Default")
      (node (ref "J40") (pin "24") (pinfunction "24_24") (pintype "passive+no_connect"))
    )
    (net (code "95") (name "unconnected-(J40-Pad25)") (class "Default")
      (node (ref "J40") (pin "25") (pinfunction "25_25") (pintype "passive+no_connect"))
    )
    (net (code "96") (name "unconnected-(J40-Pad29)") (class "Default")
      (node (ref "J40") (pin "29") (pinfunction "29_29") (pintype "passive+no_connect"))
    )
    (net (code "97") (name "unconnected-(J40-Pad38)") (class "Default")
      (node (ref "J40") (pin "38") (pinfunction "38_38") (pintype "passive+no_connect"))
    )
    (net (code "98") (name "unconnected-(J40-Pad39)") (class "Default")
      (node (ref "J40") (pin "39") (pinfunction "39_39") (pintype "passive+no_connect"))
    )
    (net (code "99") (name "unconnected-(J40-Pad40)") (class "Default")
      (node (ref "J40") (pin "40") (pinfunction "40_40") (pintype "passive+no_connect"))
    )
    (net (code "100") (name "unconnected-(J40-Pad42)") (class "Default")
      (node (ref "J40") (pin "42") (pinfunction "42_42") (pintype "passive+no_connect"))
    )
    (net (code "101") (name "unconnected-(J40-Pad43)") (class "Default")
      (node (ref "J40") (pin "43") (pinfunction "43_43") (pintype "passive+no_connect"))
    )
    (net (code "102") (name "unconnected-(J40-Pad44)") (class "Default")
      (node (ref "J40") (pin "44") (pinfunction "44_44") (pintype "passive+no_connect"))
    )
    (net (code "103") (name "unconnected-(J40-Pad45)") (class "Default")
      (node (ref "J40") (pin "45") (pinfunction "45_45") (pintype "passive+no_connect"))
    )
    (net (code "104") (name "unconnected-(J40-Pad46)") (class "Default")
      (node (ref "J40") (pin "46") (pinfunction "46_46") (pintype "passive+no_connect"))
    )
    (net (code "105") (name "unconnected-(U37-NC-Pad9)") (class "Default")
      (node (ref "U37") (pin "9") (pinfunction "NC_9") (pintype "passive+no_connect"))
    )
    (net (code "106") (name "unconnected-(U37-NC-Pad10)") (class "Default")
      (node (ref "U37") (pin "10") (pinfunction "NC_10") (pintype "passive+no_connect"))
    )
    (net (code "107") (name "unconnected-(U37-NC-Pad13)") (class "Default")
      (node (ref "U37") (pin "13") (pinfunction "NC_13") (pintype "passive+no_connect"))
    )
    (net (code "108") (name "unconnected-(U37-NC-Pad14)") (class "Default")
      (node (ref "U37") (pin "14") (pinfunction "NC_14") (pintype "passive+no_connect"))
    )
  )
)
